# Schematic.net
KiCad netlist of a schematic drawn in EAGLE
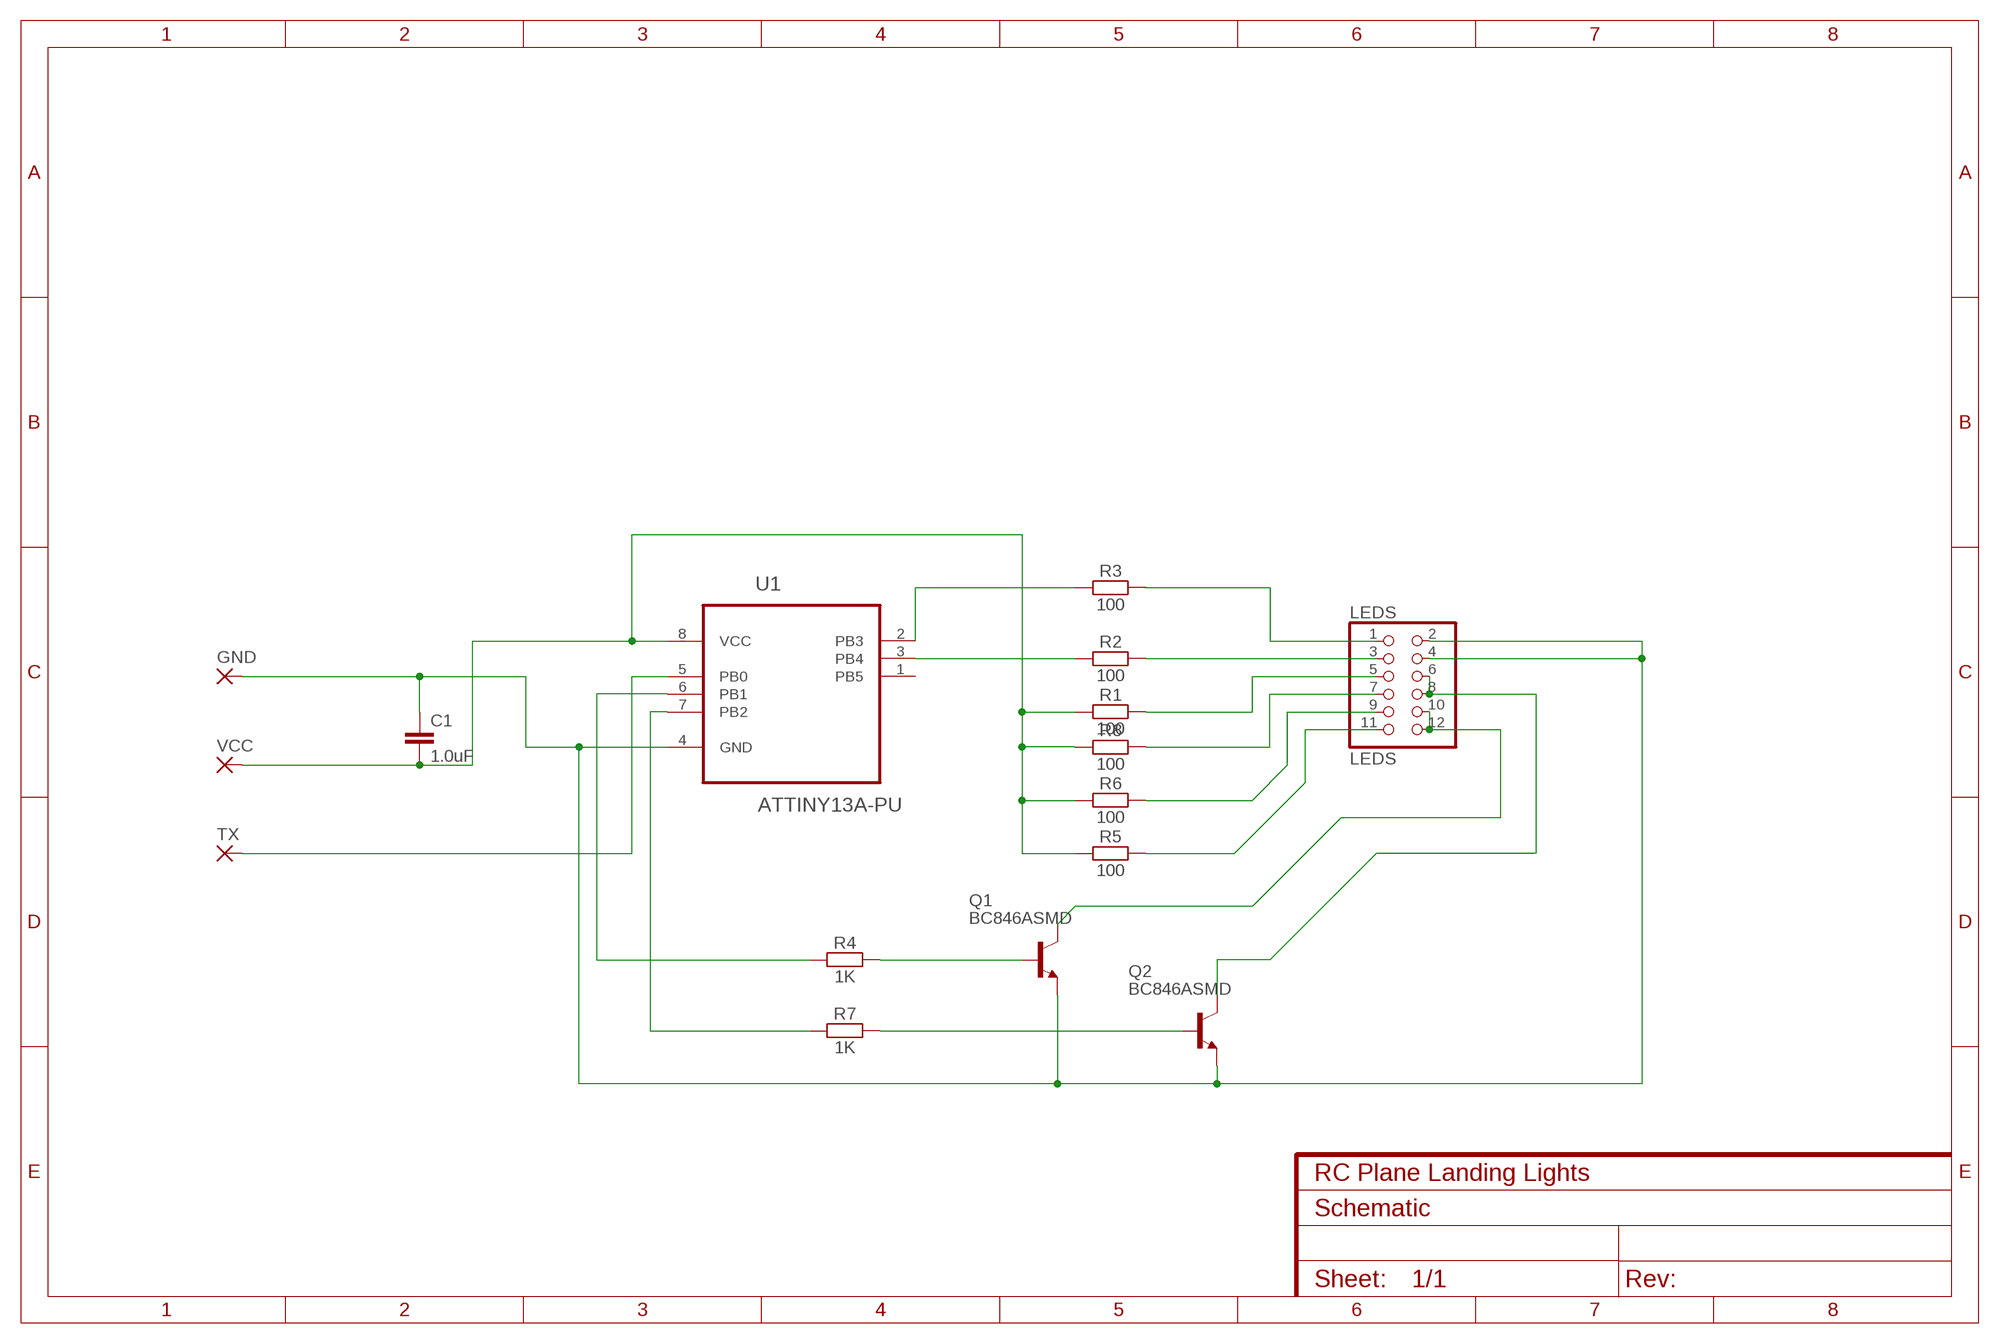
[diagram p0: schematic, sheet 1]

(export (version "E")
  (design (tool "Eeschema 10.0.6"))
  (components
    (comp (ref "C1")
      (value "1.0uF")
      (footprint "eagle-import:0805")
      (libsource (lib "eagle-import") (part "1.0UF-0805-25V-(+80/-20%)"))
    )
    (comp (ref "GND")
      (value "3,17/1,1")
      (footprint "eagle-import:3,17_1,1")
      (fields (field (name "SPICEPREFIX") "X"))
      (libsource (lib "eagle-import") (part "3,17/1,1"))
    )
    (comp (ref "LEDS")
      (value "LEDS")
      (footprint "eagle-import:2X06_90")
      (libsource (lib "eagle-import") (part "PINHD-2X06_2.54-90°"))
    )
    (comp (ref "Q1")
      (value "BC846ASMD")
      (footprint "eagle-import:SOT23")
      (libsource (lib "eagle-import") (part "BC846SMDA"))
    )
    (comp (ref "Q2")
      (value "BC846ASMD")
      (footprint "eagle-import:SOT23")
      (libsource (lib "eagle-import") (part "BC846SMDA"))
    )
    (comp (ref "R1")
      (value "100")
      (footprint "eagle-import:0805")
      (libsource (lib "eagle-import") (part "RESISTOR0805"))
    )
    (comp (ref "R2")
      (value "100")
      (footprint "eagle-import:0805")
      (libsource (lib "eagle-import") (part "RESISTOR0805"))
    )
    (comp (ref "R3")
      (value "100")
      (footprint "eagle-import:0805")
      (libsource (lib "eagle-import") (part "RESISTOR0805"))
    )
    (comp (ref "R4")
      (value "1K")
      (footprint "eagle-import:0805")
      (libsource (lib "eagle-import") (part "RESISTOR0805"))
    )
    (comp (ref "R5")
      (value "100")
      (footprint "eagle-import:0805")
      (libsource (lib "eagle-import") (part "RESISTOR0805"))
    )
    (comp (ref "R6")
      (value "100")
      (footprint "eagle-import:0805")
      (libsource (lib "eagle-import") (part "RESISTOR0805"))
    )
    (comp (ref "R7")
      (value "1K")
      (footprint "eagle-import:0805")
      (libsource (lib "eagle-import") (part "RESISTOR0805"))
    )
    (comp (ref "R8")
      (value "100")
      (footprint "eagle-import:0805")
      (libsource (lib "eagle-import") (part "RESISTOR0805"))
    )
    (comp (ref "TX")
      (value "3,17/1,1")
      (footprint "eagle-import:3,17_1,1")
      (libsource (lib "eagle-import") (part "3,17/1,1"))
    )
    (comp (ref "U1")
      (value "ATTINY13A-PU")
      (footprint "eagle-import:DIP254P762X533-8")
      (libsource (lib "eagle-import") (part "ATTINY13A-PU"))
    )
    (comp (ref "VCC")
      (value "3,17/1,1")
      (footprint "eagle-import:3,17_1,1")
      (libsource (lib "eagle-import") (part "3,17/1,1"))
    )
  )
  (nets
    (net (code "1") (name "Net-(GND-P)") (class "Default")
      (node (ref "C1") (pin "1") (pinfunction "1_1") (pintype "passive"))
      (node (ref "GND") (pin "1") (pinfunction "P_1") (pintype "passive"))
      (node (ref "LEDS") (pin "2") (pinfunction "2_2") (pintype "passive"))
      (node (ref "LEDS") (pin "4") (pinfunction "4_4") (pintype "passive"))
      (node (ref "Q1") (pin "2") (pinfunction "E_2") (pintype "passive"))
      (node (ref "Q2") (pin "2") (pinfunction "E_2") (pintype "passive"))
      (node (ref "U1") (pin "4") (pinfunction "GND_4") (pintype "passive"))
    )
    (net (code "2") (name "Net-(LEDS-Pad1)") (class "Default")
      (node (ref "LEDS") (pin "1") (pinfunction "1_1") (pintype "passive"))
      (node (ref "R3") (pin "2") (pinfunction "2_2") (pintype "passive"))
    )
    (net (code "3") (name "Net-(LEDS-Pad3)") (class "Default")
      (node (ref "LEDS") (pin "3") (pinfunction "3_3") (pintype "passive"))
      (node (ref "R2") (pin "2") (pinfunction "2_2") (pintype "passive"))
    )
    (net (code "4") (name "Net-(LEDS-Pad5)") (class "Default")
      (node (ref "LEDS") (pin "5") (pinfunction "5_5") (pintype "passive"))
      (node (ref "R1") (pin "2") (pinfunction "2_2") (pintype "passive"))
    )
    (net (code "5") (name "Net-(LEDS-Pad7)") (class "Default")
      (node (ref "LEDS") (pin "7") (pinfunction "7_7") (pintype "passive"))
      (node (ref "R8") (pin "2") (pinfunction "2_2") (pintype "passive"))
    )
    (net (code "6") (name "Net-(LEDS-Pad9)") (class "Default")
      (node (ref "LEDS") (pin "9") (pinfunction "9_9") (pintype "passive"))
      (node (ref "R6") (pin "2") (pinfunction "2_2") (pintype "passive"))
    )
    (net (code "7") (name "Net-(LEDS-Pad11)") (class "Default")
      (node (ref "LEDS") (pin "11") (pinfunction "11_11") (pintype "passive"))
      (node (ref "R5") (pin "2") (pinfunction "2_2") (pintype "passive"))
    )
    (net (code "8") (name "Net-(Q1-B)") (class "Default")
      (node (ref "Q1") (pin "1") (pinfunction "B_1") (pintype "passive"))
      (node (ref "R4") (pin "2") (pinfunction "2_2") (pintype "passive"))
    )
    (net (code "9") (name "Net-(Q1-C)") (class "Default")
      (node (ref "LEDS") (pin "10") (pinfunction "10_10") (pintype "passive"))
      (node (ref "LEDS") (pin "12") (pinfunction "12_12") (pintype "passive"))
      (node (ref "Q1") (pin "3") (pinfunction "C_3") (pintype "passive"))
    )
    (net (code "10") (name "Net-(Q2-B)") (class "Default")
      (node (ref "Q2") (pin "1") (pinfunction "B_1") (pintype "passive"))
      (node (ref "R7") (pin "2") (pinfunction "2_2") (pintype "passive"))
    )
    (net (code "11") (name "Net-(Q2-C)") (class "Default")
      (node (ref "LEDS") (pin "6") (pinfunction "6_6") (pintype "passive"))
      (node (ref "LEDS") (pin "8") (pinfunction "8_8") (pintype "passive"))
      (node (ref "Q2") (pin "3") (pinfunction "C_3") (pintype "passive"))
    )
    (net (code "12") (name "Net-(TX-P)") (class "Default")
      (node (ref "TX") (pin "1") (pinfunction "P_1") (pintype "passive"))
      (node (ref "U1") (pin "5") (pinfunction "PB0_5") (pintype "bidirectional"))
    )
    (net (code "13") (name "Net-(U1-PB1)") (class "Default")
      (node (ref "R4") (pin "1") (pinfunction "1_1") (pintype "passive"))
      (node (ref "U1") (pin "6") (pinfunction "PB1_6") (pintype "bidirectional"))
    )
    (net (code "14") (name "Net-(U1-PB2)") (class "Default")
      (node (ref "R7") (pin "1") (pinfunction "1_1") (pintype "passive"))
      (node (ref "U1") (pin "7") (pinfunction "PB2_7") (pintype "bidirectional"))
    )
    (net (code "15") (name "Net-(U1-PB3)") (class "Default")
      (node (ref "R3") (pin "1") (pinfunction "1_1") (pintype "passive"))
      (node (ref "U1") (pin "2") (pinfunction "PB3_2") (pintype "bidirectional"))
    )
    (net (code "16") (name "Net-(U1-PB4)") (class "Default")
      (node (ref "R2") (pin "1") (pinfunction "1_1") (pintype "passive"))
      (node (ref "U1") (pin "3") (pinfunction "PB4_3") (pintype "bidirectional"))
    )
    (net (code "17") (name "Net-(U1-VCC)") (class "Default")
      (node (ref "C1") (pin "2") (pinfunction "2_2") (pintype "passive"))
      (node (ref "R1") (pin "1") (pinfunction "1_1") (pintype "passive"))
      (node (ref "R5") (pin "1") (pinfunction "1_1") (pintype "passive"))
      (node (ref "R6") (pin "1") (pinfunction "1_1") (pintype "passive"))
      (node (ref "R8") (pin "1") (pinfunction "1_1") (pintype "passive"))
      (node (ref "U1") (pin "8") (pinfunction "VCC_8") (pintype "power_in"))
      (node (ref "VCC") (pin "1") (pinfunction "P_1") (pintype "passive"))
    )
    (net (code "18") (name "unconnected-(U1-PB5-Pad1)") (class "Default")
      (node (ref "U1") (pin "1") (pinfunction "PB5_1") (pintype "bidirectional"))
    )
  )
)
